# DoorCard.net
KiCad netlist of a schematic drawn in Altium Designer
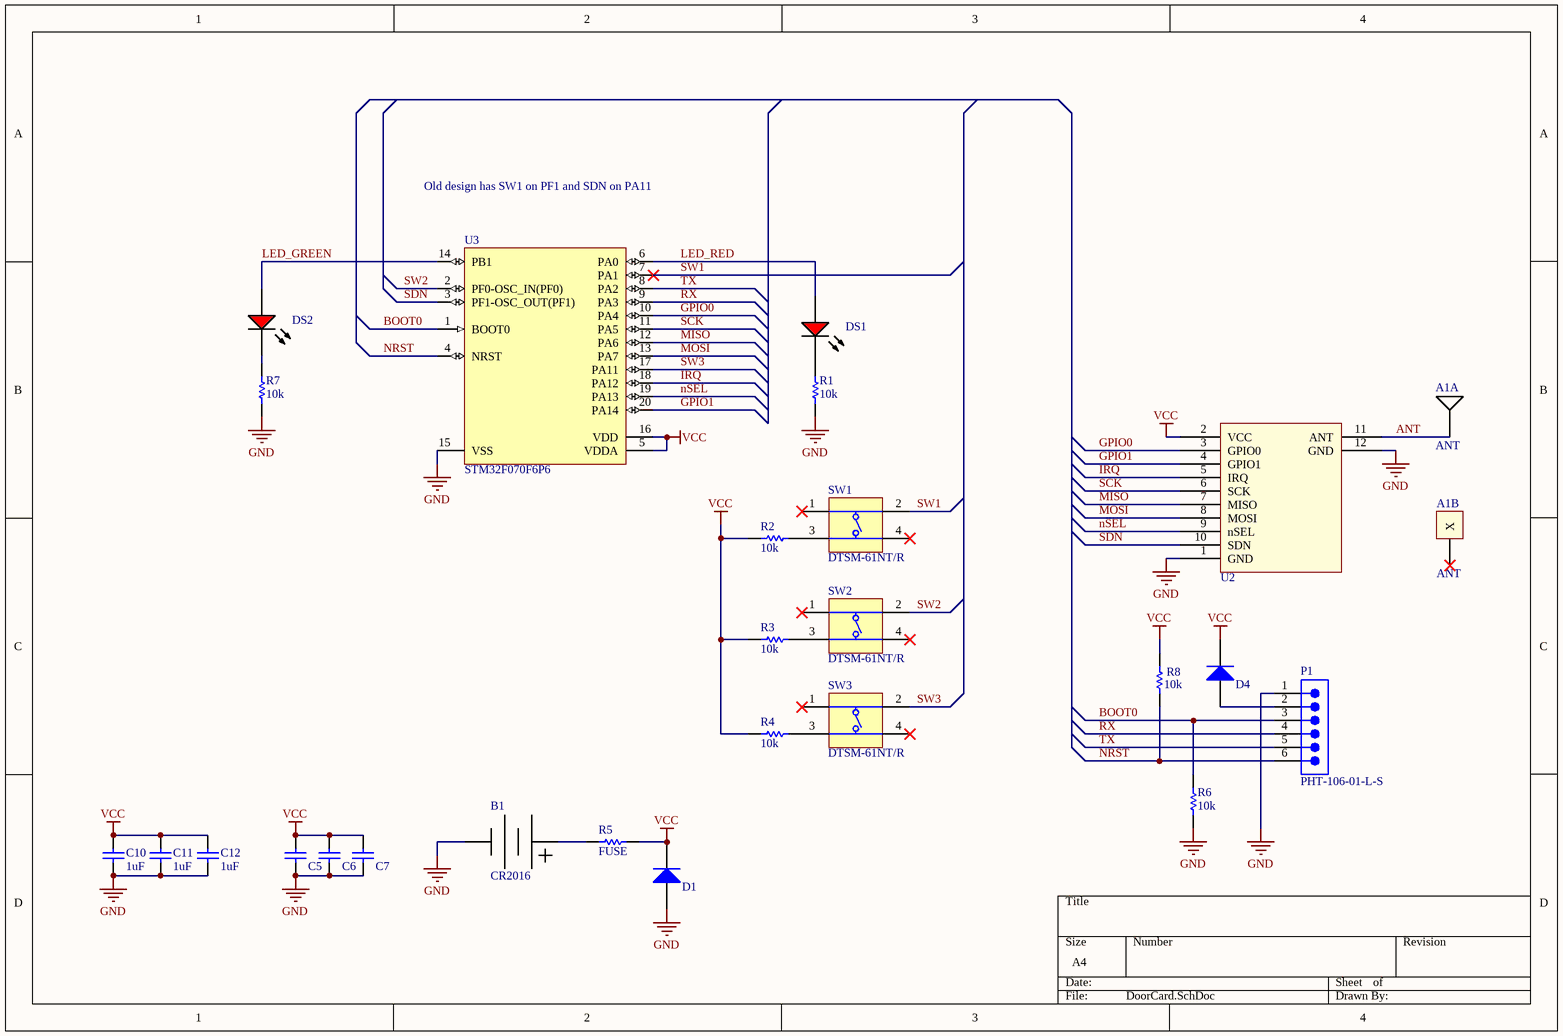
[diagram p0: DoorCard.SchDoc]

(export (version "E")
  (design (tool "Eeschema 10.0.6"))
  (components
    (comp (ref "A1")
      (value "ANT")
      (footprint "433MHz_Antenna")
      (description "ANT1204F002R0433A")
      (libsource (lib "Antenna") (part "ANT1204F002R0433A"))
    )
    (comp (ref "B1")
      (value "CR2016")
      (footprint "CR2012")
      (description "BAT-HLD-002-SMT")
      (libsource (lib "Cell") (part "BAT-HLD-002-SMT"))
    )
    (comp (ref "C5")
      (value "CAP 47uF 6.3V 1206(3216)")
      (footprint "CAPC1206(3216)190_M")
      (description "CAP 47uF 6.3V ±20% 1206 (3216 Metric) Thickness 1.9mm SMD")
      (fields (field (name "TOLERANCE") "Â±20%"))
      (libsource (lib "Altium Content Vault") (part "CMP-1037-05000-1"))
    )
    (comp (ref "C6")
      (value "CAP 47uF 6.3V 1206(3216)")
      (footprint "CAPC1206(3216)190_M")
      (description "CAP 47uF 6.3V ±20% 1206 (3216 Metric) Thickness 1.9mm SMD")
      (fields (field (name "TOLERANCE") "Â±20%"))
      (libsource (lib "Altium Content Vault") (part "CMP-1037-05000-1"))
    )
    (comp (ref "C7")
      (value "CAP 47uF 6.3V 1206(3216)")
      (footprint "CAPC1206(3216)190_M")
      (description "CAP 47uF 6.3V ±20% 1206 (3216 Metric) Thickness 1.9mm SMD")
      (fields (field (name "TOLERANCE") "Â±20%"))
      (libsource (lib "Altium Content Vault") (part "CMP-1037-05000-1"))
    )
    (comp (ref "C10")
      (value "1uF")
      (footprint "CAPC0805(2012)100_M")
      (description "CAP 1uF 25V ±10% 0805 (2012 Metric) Thickness 1mm SMD")
      (fields (field (name "TOLERANCE") "Â±10%"))
      (libsource (lib "Altium Content Vault") (part "CAP"))
    )
    (comp (ref "C11")
      (value "1uF")
      (footprint "CAPC0805(2012)100_M")
      (description "CAP 1uF 25V ±10% 0805 (2012 Metric) Thickness 1mm SMD")
      (fields (field (name "TOLERANCE") "Â±10%"))
      (libsource (lib "Altium Content Vault") (part "CAP"))
    )
    (comp (ref "C12")
      (value "1uF")
      (footprint "CAPC0805(2012)100_M")
      (description "CAP 1uF 25V ±10% 0805 (2012 Metric) Thickness 1mm SMD")
      (fields (field (name "TOLERANCE") "Â±10%"))
      (libsource (lib "Altium Content Vault") (part "CAP"))
    )
    (comp (ref "D1")
      (value "MMSD4148T3G")
      (footprint "ONSC-SOD123-2-425G-04_V")
      (description "Switching Diode, 100 V, 200 mA, -55 to 150 degC, 2-Pin SOD123 (425), RoHS, Tape and Reel")
      (fields (field (name "MANUFACTURER") "ON Semiconductor"))
      (libsource (lib "Altium Content Vault") (part "ONSC-MMSD4148-SOD123-2"))
    )
    (comp (ref "D4")
      (value "MMSD4148T3G")
      (footprint "ONSC-SOD123-2-425G-04_V")
      (description "Switching Diode, 100 V, 200 mA, -55 to 150 degC, 2-Pin SOD123 (425), RoHS, Tape and Reel")
      (fields (field (name "MANUFACTURER") "ON Semiconductor"))
      (libsource (lib "Altium Content Vault") (part "ONSC-MMSD4148-SOD123-2"))
    )
    (comp (ref "DS1")
      (value "TLMS1100-GS08")
      (footprint "VISH-TLMX1100_V")
      (description "LED, RED, 2.1 V, -40 to 100 degC, 2-Pin SMD (0603), RoHS, Tape and Reel")
      (fields (field (name "TOLERANCE") "5%"))
      (libsource (lib "Altium Content Vault") (part "LED-RED-AK-2"))
    )
    (comp (ref "DS2")
      (value "TLMS1100-GS08")
      (footprint "VISH-TLMX1100_V")
      (description "LED, RED, 2.1 V, -40 to 100 degC, 2-Pin SMD (0603), RoHS, Tape and Reel")
      (fields (field (name "TOLERANCE") "5%"))
      (libsource (lib "Altium Content Vault") (part "LED-RED-AK-2"))
    )
    (comp (ref "P1")
      (value "PHT-106-01-L-S")
      (footprint "SMTC-PHT-106-01-X-S")
      (description "Press Fit Header, Through-hole, Vertical, -55 to 125 degC, 2.54 mm Pitch, 6-Pin, Male, RoHS")
      (fields (field (name "MANUFACTURER") "Samtec"))
      (libsource (lib "Altium Content Vault") (part "SMTC-PHT-106-01-X-S"))
    )
    (comp (ref "R1")
      (value "10k")
      (footprint "RESC0805(2012)_L")
      (description "10K2 0.125W 1% 0805 (2012 Metric)  SMD")
      (fields (field (name "TOLERANCE") "1 %") (field (name "POWER") "0.125 W"))
      (libsource (lib "Altium Content Vault") (part "RES"))
    )
    (comp (ref "R2")
      (value "10k")
      (footprint "RESC0805(2012)_L")
      (description "10K2 0.125W 1% 0805 (2012 Metric)  SMD")
      (fields (field (name "TOLERANCE") "1 %") (field (name "POWER") "0.125 W"))
      (libsource (lib "Altium Content Vault") (part "RES"))
    )
    (comp (ref "R3")
      (value "10k")
      (footprint "RESC0805(2012)_L")
      (description "10K2 0.125W 1% 0805 (2012 Metric)  SMD")
      (fields (field (name "TOLERANCE") "1 %") (field (name "POWER") "0.125 W"))
      (libsource (lib "Altium Content Vault") (part "RES"))
    )
    (comp (ref "R4")
      (value "10k")
      (footprint "RESC0805(2012)_L")
      (description "10K2 0.125W 1% 0805 (2012 Metric)  SMD")
      (fields (field (name "TOLERANCE") "1 %") (field (name "POWER") "0.125 W"))
      (libsource (lib "Altium Content Vault") (part "RES"))
    )
    (comp (ref "R5")
      (value "FUSE")
      (footprint "RESC0805(2012)_L")
      (description "PTC Fuse")
      (fields (field (name "TOLERANCE") "1 %") (field (name "POWER") "0.125 W"))
      (libsource (lib "Altium Content Vault") (part "RES"))
    )
    (comp (ref "R6")
      (value "10k")
      (footprint "RESC0805(2012)_L")
      (description "10K2 0.125W 1% 0805 (2012 Metric)  SMD")
      (fields (field (name "TOLERANCE") "1 %") (field (name "POWER") "0.125 W"))
      (libsource (lib "Altium Content Vault") (part "RES"))
    )
    (comp (ref "R7")
      (value "10k")
      (footprint "RESC0805(2012)_L")
      (description "10K2 0.125W 1% 0805 (2012 Metric)  SMD")
      (fields (field (name "TOLERANCE") "1 %") (field (name "POWER") "0.125 W"))
      (libsource (lib "Altium Content Vault") (part "RES"))
    )
    (comp (ref "R8")
      (value "10k")
      (footprint "RESC0805(2012)_L")
      (description "10K2 0.125W 1% 0805 (2012 Metric)  SMD")
      (fields (field (name "TOLERANCE") "1 %") (field (name "POWER") "0.125 W"))
      (libsource (lib "Altium Content Vault") (part "RES"))
    )
    (comp (ref "SW1")
      (value "DTSM-61NT/R")
      (footprint "DIPT-DTSM-6_V")
      (description "Switch, SPNO Push Button SMD")
      (fields (field (name "MANUFACTURER") "Diptronics"))
      (libsource (lib "Altium Content Vault") (part "DIPT-DTSM-6"))
    )
    (comp (ref "SW2")
      (value "DTSM-61NT/R")
      (footprint "DIPT-DTSM-6_V")
      (description "Switch, SPNO Push Button SMD")
      (fields (field (name "MANUFACTURER") "Diptronics"))
      (libsource (lib "Altium Content Vault") (part "DIPT-DTSM-6"))
    )
    (comp (ref "SW3")
      (value "DTSM-61NT/R")
      (footprint "DIPT-DTSM-6_V")
      (description "Switch, SPNO Push Button SMD")
      (fields (field (name "MANUFACTURER") "Diptronics"))
      (libsource (lib "Altium Content Vault") (part "DIPT-DTSM-6"))
    )
    (comp (ref "U2")
      (value "Si4463")
      (footprint "E10-433MS")
      (description "E10-433MS")
      (libsource (lib "SiliconLabs") (part "Component_1"))
    )
    (comp (ref "U3")
      (value "STM32F070F6P6")
      (footprint "STM-TSSOP20_M")
      (fields (field (name "MANUFACTURER") "STMicroelectronics"))
      (libsource (lib "Altium Content Vault") (part "MC-ARM-STM32F070-TSSOP20"))
    )
  )
  (nets
    (net (code "1") (name "/ANT") (class "Default")
      (node (ref "A1") (pin "1") (pinfunction "ANT_1") (pintype "passive"))
      (node (ref "U2") (pin "11") (pinfunction "ANT_11") (pintype "passive"))
    )
    (net (code "2") (name "/BOOT0") (class "Default")
      (node (ref "P1") (pin "3") (pinfunction "3_3") (pintype "passive"))
      (node (ref "R6") (pin "2") (pinfunction "2_2") (pintype "passive"))
      (node (ref "U3") (pin "1") (pinfunction "BOOT0_1") (pintype "input"))
    )
    (net (code "3") (name "/GPIO0") (class "Default")
      (node (ref "U2") (pin "3") (pinfunction "GPIO0_3") (pintype "passive"))
      (node (ref "U3") (pin "10") (pinfunction "PA4_10") (pintype "bidirectional"))
    )
    (net (code "4") (name "/GPIO1") (class "Default")
      (node (ref "U2") (pin "4") (pinfunction "GPIO1_4") (pintype "passive"))
      (node (ref "U3") (pin "20") (pinfunction "PA14_20") (pintype "bidirectional"))
    )
    (net (code "5") (name "/IRQ") (class "Default")
      (node (ref "U2") (pin "5") (pinfunction "IRQ_5") (pintype "passive"))
      (node (ref "U3") (pin "18") (pinfunction "PA12_18") (pintype "bidirectional"))
    )
    (net (code "6") (name "/LED_GREEN") (class "Default")
      (node (ref "DS2") (pin "1") (pinfunction "A_1") (pintype "passive"))
      (node (ref "U3") (pin "14") (pinfunction "PB1_14") (pintype "bidirectional"))
    )
    (net (code "7") (name "/LED_RED") (class "Default")
      (node (ref "DS1") (pin "1") (pinfunction "A_1") (pintype "passive"))
      (node (ref "U3") (pin "6") (pinfunction "PA0_6") (pintype "bidirectional"))
    )
    (net (code "8") (name "/MISO") (class "Default")
      (node (ref "U2") (pin "7") (pinfunction "MISO_7") (pintype "passive"))
      (node (ref "U3") (pin "12") (pinfunction "PA6_12") (pintype "bidirectional"))
    )
    (net (code "9") (name "/MOSI") (class "Default")
      (node (ref "U2") (pin "8") (pinfunction "MOSI_8") (pintype "passive"))
      (node (ref "U3") (pin "13") (pinfunction "PA7_13") (pintype "bidirectional"))
    )
    (net (code "10") (name "/NRST") (class "Default")
      (node (ref "P1") (pin "6") (pinfunction "6_6") (pintype "passive"))
      (node (ref "R8") (pin "1") (pinfunction "1_1") (pintype "passive"))
      (node (ref "U3") (pin "4") (pinfunction "NRST_4") (pintype "bidirectional"))
    )
    (net (code "11") (name "/RX") (class "Default")
      (node (ref "P1") (pin "4") (pinfunction "4_4") (pintype "passive"))
      (node (ref "U3") (pin "9") (pinfunction "PA3_9") (pintype "bidirectional"))
    )
    (net (code "12") (name "/SCK") (class "Default")
      (node (ref "U2") (pin "6") (pinfunction "SCK_6") (pintype "passive"))
      (node (ref "U3") (pin "11") (pinfunction "PA5_11") (pintype "bidirectional"))
    )
    (net (code "13") (name "/SDN") (class "Default")
      (node (ref "U2") (pin "10") (pinfunction "SDN_10") (pintype "passive"))
      (node (ref "U3") (pin "3") (pinfunction "PF1-OSC_OUT(PF1)_3") (pintype "bidirectional"))
    )
    (net (code "14") (name "/SW1") (class "Default")
      (node (ref "SW1") (pin "2") (pinfunction "T2_2") (pintype "passive"))
      (node (ref "U3") (pin "7") (pinfunction "PA1_7") (pintype "bidirectional"))
    )
    (net (code "15") (name "/SW2") (class "Default")
      (node (ref "SW2") (pin "2") (pinfunction "T2_2") (pintype "passive"))
      (node (ref "U3") (pin "2") (pinfunction "PF0-OSC_IN(PF0)_2") (pintype "bidirectional"))
    )
    (net (code "16") (name "/SW3") (class "Default")
      (node (ref "SW3") (pin "2") (pinfunction "T2_2") (pintype "passive"))
      (node (ref "U3") (pin "17") (pinfunction "PA11_17") (pintype "bidirectional"))
    )
    (net (code "17") (name "/TX") (class "Default")
      (node (ref "P1") (pin "5") (pinfunction "5_5") (pintype "passive"))
      (node (ref "U3") (pin "8") (pinfunction "PA2_8") (pintype "bidirectional"))
    )
    (net (code "18") (name "/nSEL") (class "Default")
      (node (ref "U2") (pin "9") (pinfunction "nSEL_9") (pintype "passive"))
      (node (ref "U3") (pin "19") (pinfunction "PA13_19") (pintype "bidirectional"))
    )
    (net (code "19") (name "GND") (class "Default")
      (node (ref "B1") (pin "2") (pinfunction "2_2") (pintype "passive"))
      (node (ref "C10") (pin "1") (pinfunction "1_1") (pintype "passive"))
      (node (ref "C11") (pin "1") (pinfunction "1_1") (pintype "passive"))
      (node (ref "C12") (pin "1") (pinfunction "1_1") (pintype "passive"))
      (node (ref "C5") (pin "1") (pinfunction "1_1") (pintype "passive"))
      (node (ref "C6") (pin "1") (pinfunction "1_1") (pintype "passive"))
      (node (ref "C7") (pin "1") (pinfunction "1_1") (pintype "passive"))
      (node (ref "D1") (pin "2") (pinfunction "ANODE_2") (pintype "passive"))
      (node (ref "P1") (pin "1") (pinfunction "1_1") (pintype "passive"))
      (node (ref "R1") (pin "1") (pinfunction "1_1") (pintype "passive"))
      (node (ref "R6") (pin "1") (pinfunction "1_1") (pintype "passive"))
      (node (ref "R7") (pin "1") (pinfunction "1_1") (pintype "passive"))
      (node (ref "U2") (pin "1") (pinfunction "GND_1") (pintype "passive"))
      (node (ref "U2") (pin "12") (pinfunction "GND_12") (pintype "passive"))
      (node (ref "U3") (pin "15") (pinfunction "VSS_15") (pintype "power_in"))
    )
    (net (code "20") (name "Net-(B1-Pad1)") (class "Default")
      (node (ref "B1") (pin "1") (pinfunction "1_1") (pintype "passive"))
      (node (ref "R5") (pin "2") (pinfunction "2_2") (pintype "passive"))
    )
    (net (code "21") (name "Net-(D4-ANODE)") (class "Default")
      (node (ref "D4") (pin "2") (pinfunction "ANODE_2") (pintype "passive"))
      (node (ref "P1") (pin "2") (pinfunction "2_2") (pintype "passive"))
    )
    (net (code "22") (name "Net-(DS1-K)") (class "Default")
      (node (ref "DS1") (pin "2") (pinfunction "K_2") (pintype "passive"))
      (node (ref "R1") (pin "2") (pinfunction "2_2") (pintype "passive"))
    )
    (net (code "23") (name "Net-(DS2-K)") (class "Default")
      (node (ref "DS2") (pin "2") (pinfunction "K_2") (pintype "passive"))
      (node (ref "R7") (pin "2") (pinfunction "2_2") (pintype "passive"))
    )
    (net (code "24") (name "Net-(R2-Pad1)") (class "Default")
      (node (ref "R2") (pin "1") (pinfunction "1_1") (pintype "passive"))
      (node (ref "SW1") (pin "3") (pinfunction "T3_3") (pintype "passive"))
    )
    (net (code "25") (name "Net-(R3-Pad2)") (class "Default")
      (node (ref "R3") (pin "2") (pinfunction "2_2") (pintype "passive"))
      (node (ref "SW2") (pin "3") (pinfunction "T3_3") (pintype "passive"))
    )
    (net (code "26") (name "Net-(R4-Pad1)") (class "Default")
      (node (ref "R4") (pin "1") (pinfunction "1_1") (pintype "passive"))
      (node (ref "SW3") (pin "3") (pinfunction "T3_3") (pintype "passive"))
    )
    (net (code "27") (name "VCC") (class "Default")
      (node (ref "C10") (pin "2") (pinfunction "2_2") (pintype "passive"))
      (node (ref "C11") (pin "2") (pinfunction "2_2") (pintype "passive"))
      (node (ref "C12") (pin "2") (pinfunction "2_2") (pintype "passive"))
      (node (ref "C5") (pin "2") (pinfunction "2_2") (pintype "passive"))
      (node (ref "C6") (pin "2") (pinfunction "2_2") (pintype "passive"))
      (node (ref "C7") (pin "2") (pinfunction "2_2") (pintype "passive"))
      (node (ref "D1") (pin "1") (pinfunction "CATHODE_1") (pintype "passive"))
      (node (ref "D4") (pin "1") (pinfunction "CATHODE_1") (pintype "passive"))
      (node (ref "R2") (pin "2") (pinfunction "2_2") (pintype "passive"))
      (node (ref "R3") (pin "1") (pinfunction "1_1") (pintype "passive"))
      (node (ref "R4") (pin "2") (pinfunction "2_2") (pintype "passive"))
      (node (ref "R5") (pin "1") (pinfunction "1_1") (pintype "passive"))
      (node (ref "R8") (pin "2") (pinfunction "2_2") (pintype "passive"))
      (node (ref "U2") (pin "2") (pinfunction "VCC_2") (pintype "passive"))
      (node (ref "U3") (pin "16") (pinfunction "VDD_16") (pintype "power_in"))
      (node (ref "U3") (pin "5") (pinfunction "VDDA_5") (pintype "power_in"))
    )
    (net (code "28") (name "unconnected-(A1B-X-Pad2)") (class "Default")
      (node (ref "A1") (pin "2") (pinfunction "X_2") (pintype "passive+no_connect"))
    )
    (net (code "29") (name "unconnected-(SW1-T1-Pad1)") (class "Default")
      (node (ref "SW1") (pin "1") (pinfunction "T1_1") (pintype "passive+no_connect"))
    )
    (net (code "30") (name "unconnected-(SW1-T3-Pad4)") (class "Default")
      (node (ref "SW1") (pin "4") (pinfunction "T3_4") (pintype "passive+no_connect"))
    )
    (net (code "31") (name "unconnected-(SW2-T1-Pad1)") (class "Default")
      (node (ref "SW2") (pin "1") (pinfunction "T1_1") (pintype "passive+no_connect"))
    )
    (net (code "32") (name "unconnected-(SW2-T3-Pad4)") (class "Default")
      (node (ref "SW2") (pin "4") (pinfunction "T3_4") (pintype "passive+no_connect"))
    )
    (net (code "33") (name "unconnected-(SW3-T1-Pad1)") (class "Default")
      (node (ref "SW3") (pin "1") (pinfunction "T1_1") (pintype "passive+no_connect"))
    )
    (net (code "34") (name "unconnected-(SW3-T3-Pad4)") (class "Default")
      (node (ref "SW3") (pin "4") (pinfunction "T3_4") (pintype "passive+no_connect"))
    )
  )
)
